# 2017-09-15_drum_circuits.net
KiCad netlist of a schematic drawn in EAGLE
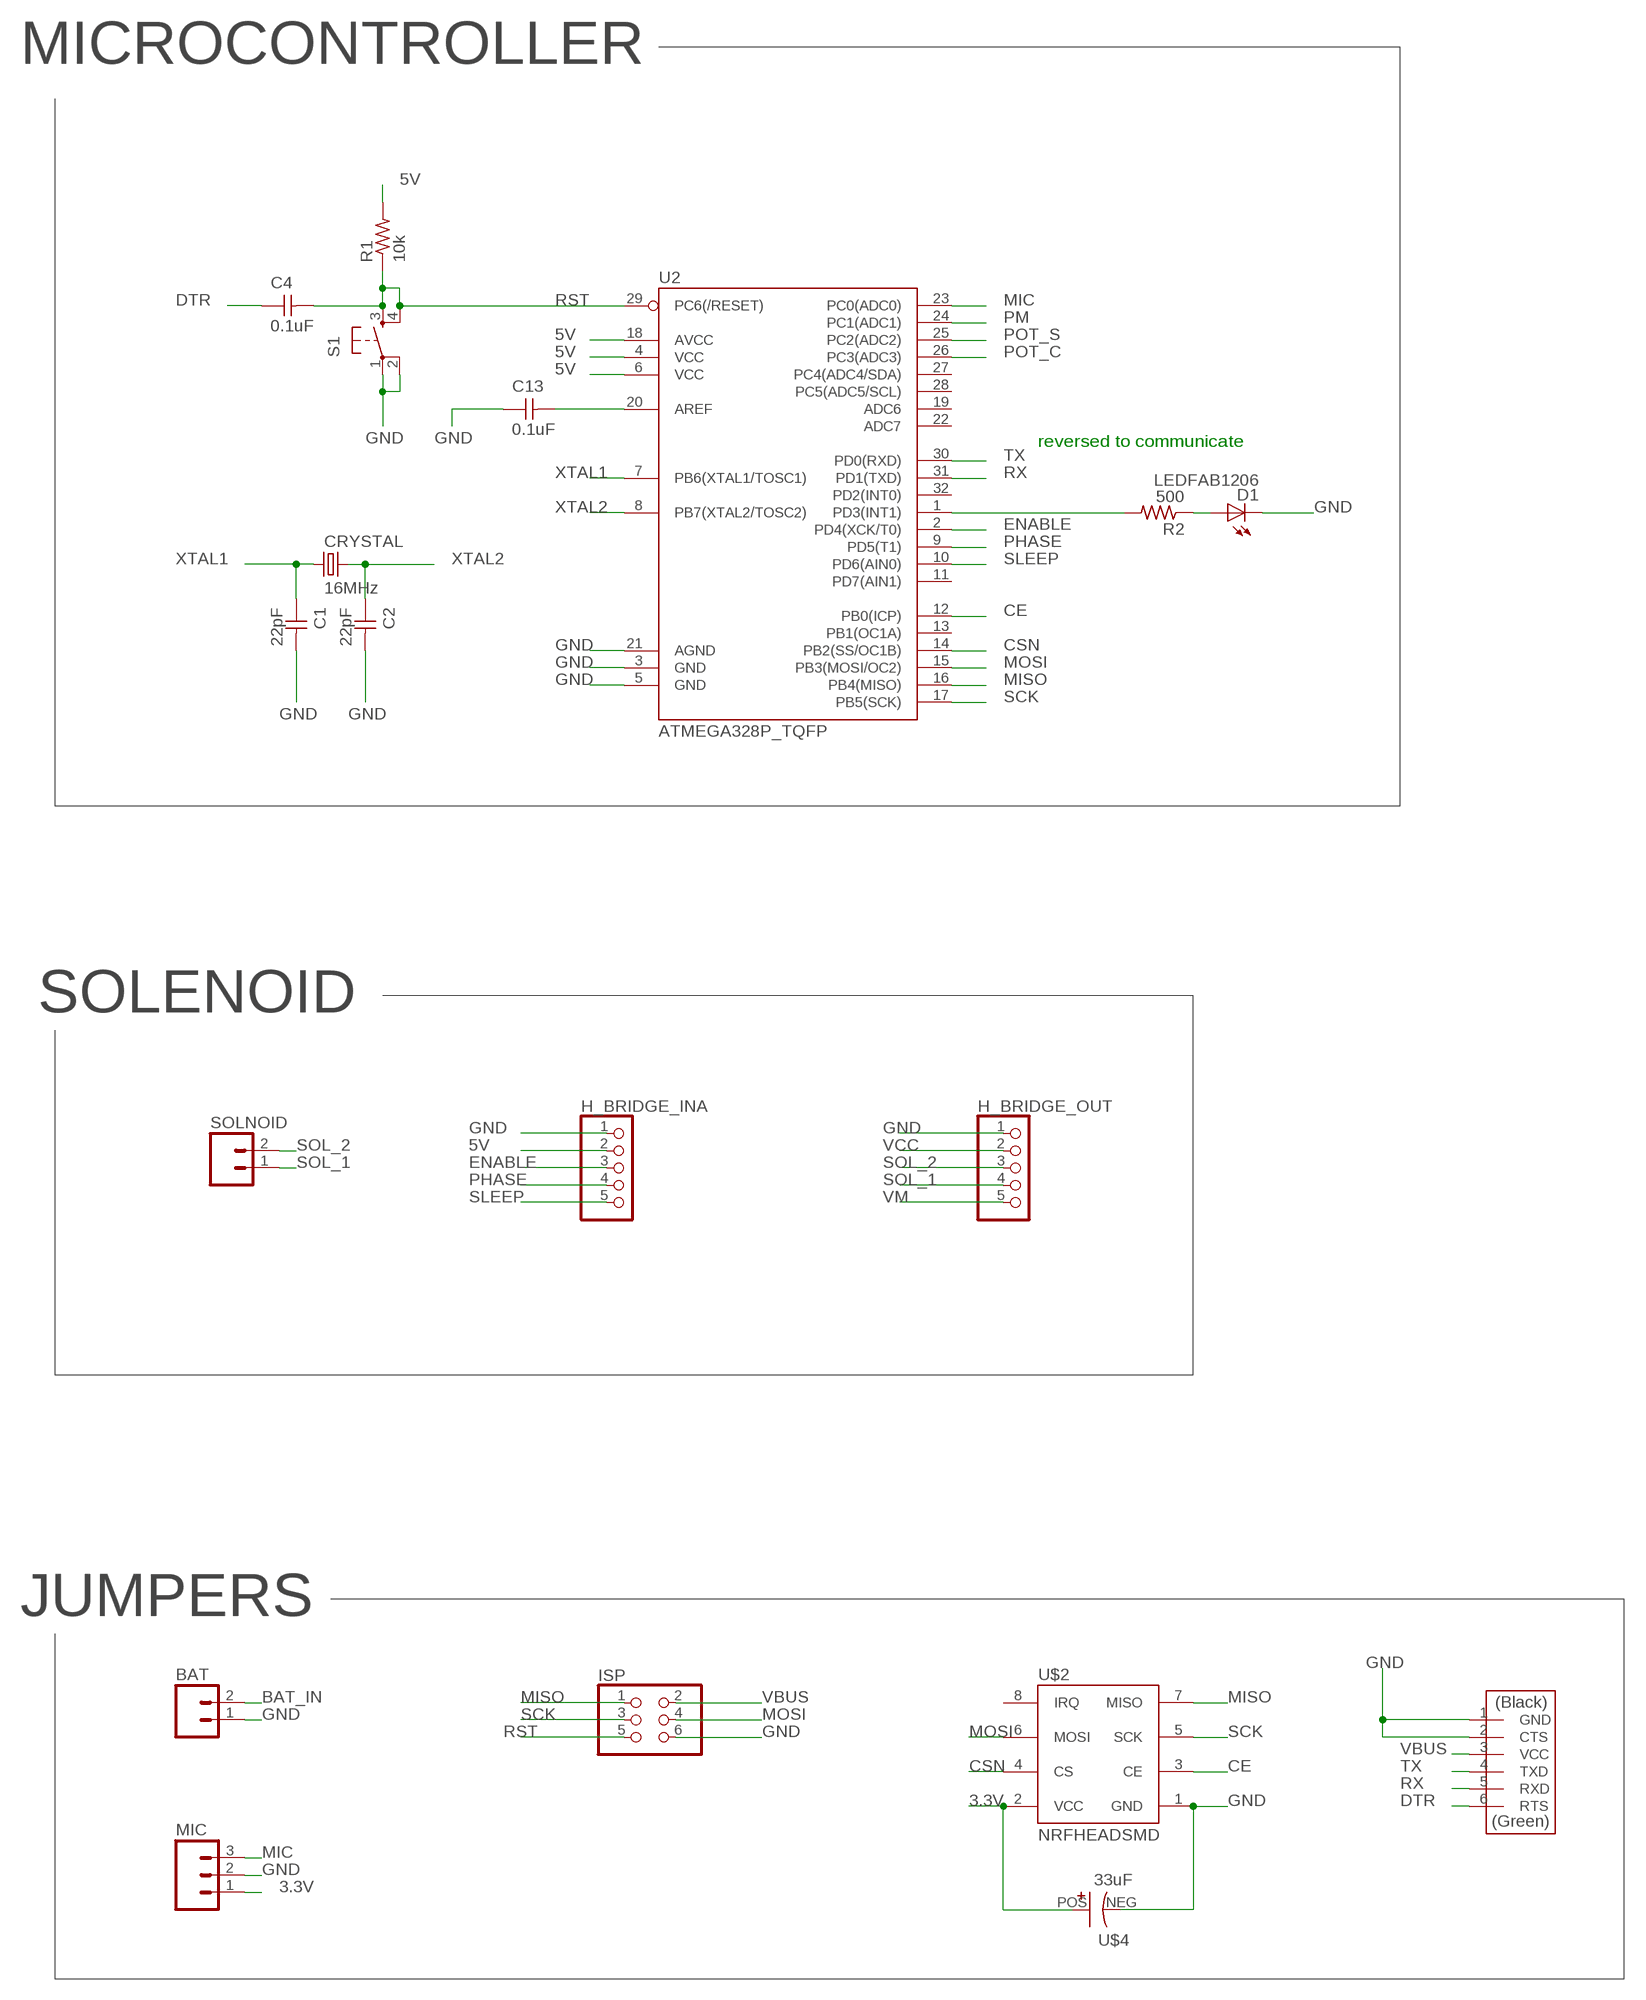
[diagram p0: schematic, sheet 1, part 1 of 2]
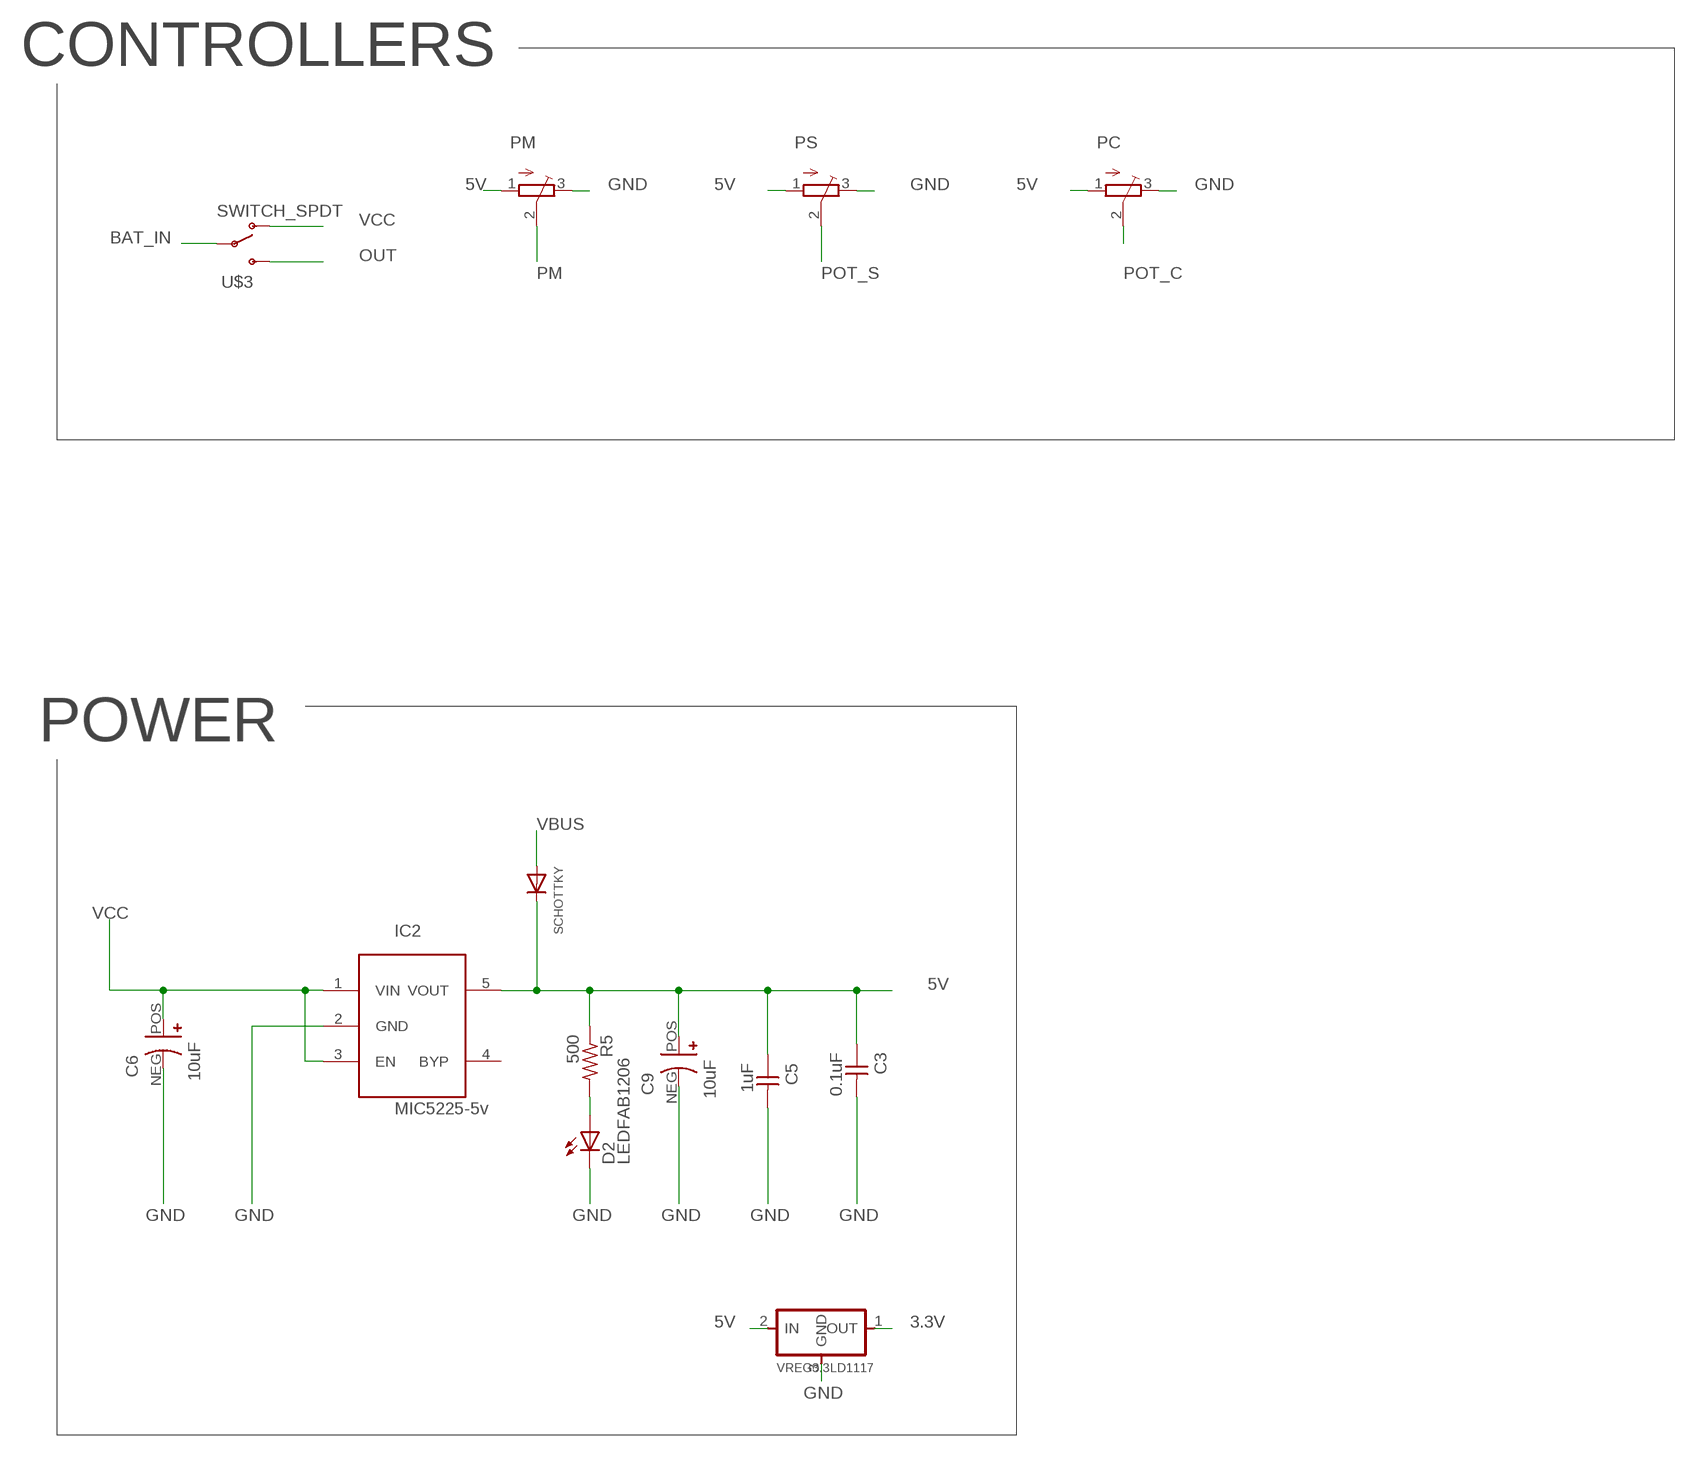
[diagram p1: schematic, sheet 1, part 2 of 2]

(export (version "E")
  (design (tool "Eeschema 10.0.6"))
  (components
    (comp (ref "BAT")
      (value "M02PTH")
      (footprint "eagle-import:1X02")
      (libsource (lib "eagle-import") (part "M02PTH"))
    )
    (comp (ref "C1")
      (value "22pF")
      (footprint "eagle-import:C1206FAB")
      (libsource (lib "eagle-import") (part "CAP-UNPOLARIZEDFAB"))
    )
    (comp (ref "C2")
      (value "22pF")
      (footprint "eagle-import:C1206FAB")
      (libsource (lib "eagle-import") (part "CAP-UNPOLARIZEDFAB"))
    )
    (comp (ref "C3")
      (value "0.1uF")
      (footprint "eagle-import:C1206FAB")
      (libsource (lib "eagle-import") (part "CAP-UNPOLARIZEDFAB"))
    )
    (comp (ref "C4")
      (value "0.1uF")
      (footprint "eagle-import:C1206FAB")
      (libsource (lib "eagle-import") (part "CAP-UNPOLARIZEDFAB"))
    )
    (comp (ref "C5")
      (value "1uF")
      (footprint "eagle-import:C1206FAB")
      (libsource (lib "eagle-import") (part "CAP-UNPOLARIZEDFAB"))
    )
    (comp (ref "C6")
      (value "10uF")
      (footprint "eagle-import:PANASONIC-CAP-SMD-B")
      (libsource (lib "eagle-import") (part "POLCAP-PANASONIC-SMD-B01"))
    )
    (comp (ref "C9")
      (value "10uF")
      (footprint "eagle-import:PANASONIC-CAP-SMD-B")
      (libsource (lib "eagle-import") (part "POLCAP-PANASONIC-SMD-B01"))
    )
    (comp (ref "C13")
      (value "0.1uF")
      (footprint "eagle-import:C1206FAB")
      (libsource (lib "eagle-import") (part "CAP-UNPOLARIZEDFAB"))
    )
    (comp (ref "CRYSTAL")
      (value "16MHz")
      (footprint "eagle-import:2-SMD-5X3MM")
      (libsource (lib "eagle-import") (part "CRYSTAL"))
    )
    (comp (ref "D1")
      (value "LEDFAB1206")
      (footprint "eagle-import:LED1206FAB")
      (libsource (lib "eagle-import") (part "LEDFAB1206"))
    )
    (comp (ref "D2")
      (value "LEDFAB1206")
      (footprint "eagle-import:LED1206FAB")
      (libsource (lib "eagle-import") (part "LEDFAB1206"))
    )
    (comp (ref "H_BRIDGE_INA")
      (value "PINHD-1X05_2.54-SMD")
      (footprint "eagle-import:1X05SMD")
      (libsource (lib "eagle-import") (part "PINHD-1X05_2.54-SMD"))
    )
    (comp (ref "H_BRIDGE_OUT")
      (value "PINHD-1X05_2.54-SMD")
      (footprint "eagle-import:1X05SMD")
      (libsource (lib "eagle-import") (part "PINHD-1X05_2.54-SMD"))
    )
    (comp (ref "IC2")
      (value "MIC5225-5v")
      (footprint "eagle-import:SOT23-5L")
      (libsource (lib "eagle-import") (part "LP298XS"))
    )
    (comp (ref "ISP")
      (value "PINHD-2X3-SMD")
      (footprint "eagle-import:2X03SMD")
      (libsource (lib "eagle-import") (part "PINHD-2X3-SMD"))
    )
    (comp (ref "MIC")
      (value "M03PTH")
      (footprint "eagle-import:1X03")
      (libsource (lib "eagle-import") (part "M03PTH"))
    )
    (comp (ref "PC")
      (value "TRIMPOTTC33X")
      (footprint "eagle-import:TC33X")
      (libsource (lib "eagle-import") (part "TRIMPOTTC33X"))
    )
    (comp (ref "PM")
      (value "TRIMPOTTC33X")
      (footprint "eagle-import:TC33X")
      (libsource (lib "eagle-import") (part "TRIMPOTTC33X"))
    )
    (comp (ref "PS")
      (value "TRIMPOTTC33X")
      (footprint "eagle-import:TC33X")
      (libsource (lib "eagle-import") (part "TRIMPOTTC33X"))
    )
    (comp (ref "R1")
      (value "10k")
      (footprint "eagle-import:R1206FAB")
      (libsource (lib "eagle-import") (part "RES-US1206FAB"))
    )
    (comp (ref "R2")
      (value "500")
      (footprint "eagle-import:R1206FAB")
      (libsource (lib "eagle-import") (part "RES-US1206FAB"))
    )
    (comp (ref "R5")
      (value "500")
      (footprint "eagle-import:R1206FAB")
      (libsource (lib "eagle-import") (part "RES-US1206FAB"))
    )
    (comp (ref "S1")
      (value "6MM_SWITCH6MM_SWITCH")
      (footprint "eagle-import:6MM_SWITCH")
      (libsource (lib "eagle-import") (part "6MM_SWITCH6MM_SWITCH"))
    )
    (comp (ref "SCHOTTKY")
      (value "DIODE_SOD-123FL")
      (footprint "eagle-import:SOD-123FL")
      (libsource (lib "eagle-import") (part "DIODE_SOD-123FL"))
    )
    (comp (ref "SOLNOID")
      (value "M02PTH")
      (footprint "eagle-import:1X02")
      (libsource (lib "eagle-import") (part "M02PTH"))
    )
    (comp (ref "U$1")
      (value "FTDI-SMD-HEADER")
      (footprint "eagle-import:1X06SMD")
      (libsource (lib "eagle-import") (part "FTDI-SMD-HEADER"))
    )
    (comp (ref "U$2")
      (value "NRFHEADSMD")
      (footprint "eagle-import:2.54MM")
      (libsource (lib "eagle-import") (part "NRFHEADSMD"))
    )
    (comp (ref "U$3")
      (value "SWITCH_SPDT")
      (footprint "eagle-import:KPS-1290")
      (libsource (lib "eagle-import") (part "SWITCH_SPDT"))
    )
    (comp (ref "U$4")
      (value "33uF")
      (footprint "eagle-import:PANASONIC-CAP-SMD-C")
      (libsource (lib "eagle-import") (part "POLCAP-PANASONIC-SMD-C"))
    )
    (comp (ref "U2")
      (value "ATMEGA328P_TQFP")
      (footprint "eagle-import:TQFP32-08")
      (libsource (lib "eagle-import") (part "ATMEGA328P_TQFP"))
    )
    (comp (ref "VREG3.3")
      (value "LD1117")
      (footprint "eagle-import:SOT23")
      (libsource (lib "eagle-import") (part "REGULATORSOT23"))
    )
  )
  (nets
    (net (code "1") (name "/3.3V") (class "Default")
      (node (ref "MIC") (pin "1") (pinfunction "1_1") (pintype "passive"))
      (node (ref "U$2") (pin "2") (pinfunction "VCC_2") (pintype "bidirectional"))
      (node (ref "U$4") (pin "POS") (pinfunction "+_POS") (pintype "bidirectional"))
      (node (ref "VREG3.3") (pin "1") (pinfunction "OUT_1") (pintype "bidirectional"))
    )
    (net (code "2") (name "/5V") (class "Default")
      (node (ref "C3") (pin "1") (pinfunction "1_1") (pintype "passive"))
      (node (ref "C5") (pin "1") (pinfunction "1_1") (pintype "passive"))
      (node (ref "C9") (pin "POS") (pinfunction "+_POS") (pintype "bidirectional"))
      (node (ref "H_BRIDGE_INA") (pin "2") (pinfunction "2_2") (pintype "passive"))
      (node (ref "IC2") (pin "5") (pinfunction "VOUT_5") (pintype "bidirectional"))
      (node (ref "PC") (pin "1") (pinfunction "A_1") (pintype "passive"))
      (node (ref "PM") (pin "1") (pinfunction "A_1") (pintype "passive"))
      (node (ref "PS") (pin "1") (pinfunction "A_1") (pintype "passive"))
      (node (ref "R1") (pin "2") (pinfunction "2_2") (pintype "passive"))
      (node (ref "R5") (pin "1") (pinfunction "1_1") (pintype "passive"))
      (node (ref "SCHOTTKY") (pin "C") (pinfunction "C_C") (pintype "passive"))
      (node (ref "U2") (pin "18") (pinfunction "AVCC_18") (pintype "bidirectional"))
      (node (ref "U2") (pin "4") (pinfunction "VCC_4") (pintype "bidirectional"))
      (node (ref "U2") (pin "6") (pinfunction "VCC_6") (pintype "bidirectional"))
      (node (ref "VREG3.3") (pin "2") (pinfunction "IN_2") (pintype "bidirectional"))
    )
    (net (code "3") (name "/BAT_IN") (class "Default")
      (node (ref "BAT") (pin "2") (pinfunction "2_2") (pintype "passive"))
      (node (ref "U$3") (pin "P") (pinfunction "P_P") (pintype "passive"))
    )
    (net (code "4") (name "/CE") (class "Default")
      (node (ref "U$2") (pin "3") (pinfunction "CE_3") (pintype "bidirectional"))
      (node (ref "U2") (pin "12") (pinfunction "PB0(ICP)_12") (pintype "bidirectional"))
    )
    (net (code "5") (name "/CSN") (class "Default")
      (node (ref "U$2") (pin "4") (pinfunction "CS_4") (pintype "bidirectional"))
      (node (ref "U2") (pin "14") (pinfunction "PB2(SS/OC1B)_14") (pintype "bidirectional"))
    )
    (net (code "6") (name "/DTR") (class "Default")
      (node (ref "C4") (pin "1") (pinfunction "1_1") (pintype "passive"))
      (node (ref "U$1") (pin "6") (pinfunction "RTS_6") (pintype "bidirectional"))
    )
    (net (code "7") (name "/ENABLE") (class "Default")
      (node (ref "H_BRIDGE_INA") (pin "3") (pinfunction "3_3") (pintype "passive"))
      (node (ref "U2") (pin "2") (pinfunction "PD4(XCK/T0)_2") (pintype "bidirectional"))
    )
    (net (code "8") (name "/GND") (class "Default")
      (node (ref "BAT") (pin "1") (pinfunction "1_1") (pintype "passive"))
      (node (ref "C1") (pin "2") (pinfunction "2_2") (pintype "passive"))
      (node (ref "C13") (pin "1") (pinfunction "1_1") (pintype "passive"))
      (node (ref "C2") (pin "2") (pinfunction "2_2") (pintype "passive"))
      (node (ref "C3") (pin "2") (pinfunction "2_2") (pintype "passive"))
      (node (ref "C5") (pin "2") (pinfunction "2_2") (pintype "passive"))
      (node (ref "C6") (pin "NEG") (pinfunction "-_NEG") (pintype "bidirectional"))
      (node (ref "C9") (pin "NEG") (pinfunction "-_NEG") (pintype "bidirectional"))
      (node (ref "D1") (pin "2") (pinfunction "C_2") (pintype "passive"))
      (node (ref "D2") (pin "2") (pinfunction "C_2") (pintype "passive"))
      (node (ref "H_BRIDGE_INA") (pin "1") (pinfunction "1_1") (pintype "passive"))
      (node (ref "H_BRIDGE_OUT") (pin "1") (pinfunction "1_1") (pintype "passive"))
      (node (ref "IC2") (pin "2") (pinfunction "GND_2") (pintype "bidirectional"))
      (node (ref "ISP") (pin "6") (pinfunction "6_6") (pintype "passive"))
      (node (ref "MIC") (pin "2") (pinfunction "2_2") (pintype "passive"))
      (node (ref "PC") (pin "3") (pinfunction "E_3") (pintype "passive"))
      (node (ref "PM") (pin "3") (pinfunction "E_3") (pintype "passive"))
      (node (ref "PS") (pin "3") (pinfunction "E_3") (pintype "passive"))
      (node (ref "S1") (pin "1") (pinfunction "P_1") (pintype "passive"))
      (node (ref "S1") (pin "2") (pinfunction "P1_2") (pintype "passive"))
      (node (ref "U$1") (pin "1") (pinfunction "GND_1") (pintype "bidirectional"))
      (node (ref "U$1") (pin "2") (pinfunction "CTS_2") (pintype "bidirectional"))
      (node (ref "U$2") (pin "1") (pinfunction "GND_1") (pintype "bidirectional"))
      (node (ref "U$4") (pin "NEG") (pinfunction "-_NEG") (pintype "bidirectional"))
      (node (ref "U2") (pin "21") (pinfunction "AGND_21") (pintype "bidirectional"))
      (node (ref "U2") (pin "3") (pinfunction "GND_3") (pintype "bidirectional"))
      (node (ref "U2") (pin "5") (pinfunction "GND_5") (pintype "bidirectional"))
      (node (ref "VREG3.3") (pin "3") (pinfunction "GND_3") (pintype "bidirectional"))
    )
    (net (code "9") (name "/MIC") (class "Default")
      (node (ref "MIC") (pin "3") (pinfunction "3_3") (pintype "passive"))
      (node (ref "U2") (pin "23") (pinfunction "PC0(ADC0)_23") (pintype "bidirectional"))
    )
    (net (code "10") (name "/MISO") (class "Default")
      (node (ref "ISP") (pin "1") (pinfunction "1_1") (pintype "passive"))
      (node (ref "U$2") (pin "7") (pinfunction "MISO_7") (pintype "bidirectional"))
      (node (ref "U2") (pin "16") (pinfunction "PB4(MISO)_16") (pintype "bidirectional"))
    )
    (net (code "11") (name "/MOSI") (class "Default")
      (node (ref "ISP") (pin "4") (pinfunction "4_4") (pintype "passive"))
      (node (ref "U$2") (pin "6") (pinfunction "MOSI_6") (pintype "bidirectional"))
      (node (ref "U2") (pin "15") (pinfunction "PB3(MOSI/OC2)_15") (pintype "bidirectional"))
    )
    (net (code "12") (name "/OUT") (class "Default")
      (node (ref "U$3") (pin "S") (pinfunction "S_S") (pintype "passive"))
    )
    (net (code "13") (name "/PHASE") (class "Default")
      (node (ref "H_BRIDGE_INA") (pin "4") (pinfunction "4_4") (pintype "passive"))
      (node (ref "U2") (pin "9") (pinfunction "PD5(T1)_9") (pintype "bidirectional"))
    )
    (net (code "14") (name "/PM") (class "Default")
      (node (ref "PM") (pin "2") (pinfunction "S_2") (pintype "passive"))
      (node (ref "U2") (pin "24") (pinfunction "PC1(ADC1)_24") (pintype "bidirectional"))
    )
    (net (code "15") (name "/POT_C") (class "Default")
      (node (ref "PC") (pin "2") (pinfunction "S_2") (pintype "passive"))
      (node (ref "U2") (pin "26") (pinfunction "PC3(ADC3)_26") (pintype "bidirectional"))
    )
    (net (code "16") (name "/POT_S") (class "Default")
      (node (ref "PS") (pin "2") (pinfunction "S_2") (pintype "passive"))
      (node (ref "U2") (pin "25") (pinfunction "PC2(ADC2)_25") (pintype "bidirectional"))
    )
    (net (code "17") (name "/RST") (class "Default")
      (node (ref "C4") (pin "2") (pinfunction "2_2") (pintype "passive"))
      (node (ref "ISP") (pin "5") (pinfunction "5_5") (pintype "passive"))
      (node (ref "R1") (pin "1") (pinfunction "1_1") (pintype "passive"))
      (node (ref "S1") (pin "3") (pinfunction "S_3") (pintype "passive"))
      (node (ref "S1") (pin "4") (pinfunction "S1_4") (pintype "passive"))
      (node (ref "U2") (pin "29") (pinfunction "PC6(/RESET)_29") (pintype "bidirectional"))
    )
    (net (code "18") (name "/RX") (class "Default")
      (node (ref "U$1") (pin "5") (pinfunction "RXD_5") (pintype "bidirectional"))
      (node (ref "U2") (pin "31") (pinfunction "PD1(TXD)_31") (pintype "bidirectional"))
    )
    (net (code "19") (name "/SCK") (class "Default")
      (node (ref "ISP") (pin "3") (pinfunction "3_3") (pintype "passive"))
      (node (ref "U$2") (pin "5") (pinfunction "SCK_5") (pintype "bidirectional"))
      (node (ref "U2") (pin "17") (pinfunction "PB5(SCK)_17") (pintype "bidirectional"))
    )
    (net (code "20") (name "/SLEEP") (class "Default")
      (node (ref "H_BRIDGE_INA") (pin "5") (pinfunction "5_5") (pintype "passive"))
      (node (ref "U2") (pin "10") (pinfunction "PD6(AIN0)_10") (pintype "bidirectional"))
    )
    (net (code "21") (name "/SOL_1") (class "Default")
      (node (ref "H_BRIDGE_OUT") (pin "4") (pinfunction "4_4") (pintype "passive"))
      (node (ref "SOLNOID") (pin "1") (pinfunction "1_1") (pintype "passive"))
    )
    (net (code "22") (name "/SOL_2") (class "Default")
      (node (ref "H_BRIDGE_OUT") (pin "3") (pinfunction "3_3") (pintype "passive"))
      (node (ref "SOLNOID") (pin "2") (pinfunction "2_2") (pintype "passive"))
    )
    (net (code "23") (name "/TX") (class "Default")
      (node (ref "U$1") (pin "4") (pinfunction "TXD_4") (pintype "bidirectional"))
      (node (ref "U2") (pin "30") (pinfunction "PD0(RXD)_30") (pintype "bidirectional"))
    )
    (net (code "24") (name "/VBUS") (class "Default")
      (node (ref "ISP") (pin "2") (pinfunction "2_2") (pintype "passive"))
      (node (ref "SCHOTTKY") (pin "A") (pinfunction "A_A") (pintype "passive"))
      (node (ref "U$1") (pin "3") (pinfunction "VCC_3") (pintype "bidirectional"))
    )
    (net (code "25") (name "/VCC") (class "Default")
      (node (ref "C6") (pin "POS") (pinfunction "+_POS") (pintype "bidirectional"))
      (node (ref "H_BRIDGE_OUT") (pin "2") (pinfunction "2_2") (pintype "passive"))
      (node (ref "IC2") (pin "1") (pinfunction "VIN_1") (pintype "bidirectional"))
      (node (ref "IC2") (pin "3") (pinfunction "EN_3") (pintype "bidirectional"))
      (node (ref "U$3") (pin "O") (pinfunction "O_O") (pintype "passive"))
    )
    (net (code "26") (name "/VM") (class "Default")
      (node (ref "H_BRIDGE_OUT") (pin "5") (pinfunction "5_5") (pintype "passive"))
    )
    (net (code "27") (name "/XTAL1") (class "Default")
      (node (ref "C1") (pin "1") (pinfunction "1_1") (pintype "passive"))
      (node (ref "CRYSTAL") (pin "P$1") (pinfunction "1_P$1") (pintype "passive"))
      (node (ref "U2") (pin "7") (pinfunction "PB6(XTAL1/TOSC1)_7") (pintype "bidirectional"))
    )
    (net (code "28") (name "/XTAL2") (class "Default")
      (node (ref "C2") (pin "1") (pinfunction "1_1") (pintype "passive"))
      (node (ref "CRYSTAL") (pin "P$2") (pinfunction "2_P$2") (pintype "passive"))
      (node (ref "U2") (pin "8") (pinfunction "PB7(XTAL2/TOSC2)_8") (pintype "bidirectional"))
    )
    (net (code "29") (name "Net-(D1-A)") (class "Default")
      (node (ref "D1") (pin "1") (pinfunction "A_1") (pintype "passive"))
      (node (ref "R2") (pin "1") (pinfunction "1_1") (pintype "passive"))
    )
    (net (code "30") (name "Net-(D2-A)") (class "Default")
      (node (ref "D2") (pin "1") (pinfunction "A_1") (pintype "passive"))
      (node (ref "R5") (pin "2") (pinfunction "2_2") (pintype "passive"))
    )
    (net (code "31") (name "Net-(U2-AREF)") (class "Default")
      (node (ref "C13") (pin "2") (pinfunction "2_2") (pintype "passive"))
      (node (ref "U2") (pin "20") (pinfunction "AREF_20") (pintype "bidirectional"))
    )
    (net (code "32") (name "Net-(U2-PD3(INT1))") (class "Default")
      (node (ref "R2") (pin "2") (pinfunction "2_2") (pintype "passive"))
      (node (ref "U2") (pin "1") (pinfunction "PD3(INT1)_1") (pintype "bidirectional"))
    )
    (net (code "33") (name "unconnected-(IC2-BYP-Pad4)") (class "Default")
      (node (ref "IC2") (pin "4") (pinfunction "BYP_4") (pintype "bidirectional"))
    )
    (net (code "34") (name "unconnected-(U$2-IRQ-Pad8)") (class "Default")
      (node (ref "U$2") (pin "8") (pinfunction "IRQ_8") (pintype "bidirectional"))
    )
    (net (code "35") (name "unconnected-(U2-ADC6-Pad19)") (class "Default")
      (node (ref "U2") (pin "19") (pinfunction "ADC6_19") (pintype "bidirectional"))
    )
    (net (code "36") (name "unconnected-(U2-ADC7-Pad22)") (class "Default")
      (node (ref "U2") (pin "22") (pinfunction "ADC7_22") (pintype "bidirectional"))
    )
    (net (code "37") (name "unconnected-(U2-PB1(OC1A)-Pad13)") (class "Default")
      (node (ref "U2") (pin "13") (pinfunction "PB1(OC1A)_13") (pintype "bidirectional"))
    )
    (net (code "38") (name "unconnected-(U2-PC4(ADC4{slash}SDA)-Pad27)") (class "Default")
      (node (ref "U2") (pin "27") (pinfunction "PC4(ADC4/SDA)_27") (pintype "bidirectional"))
    )
    (net (code "39") (name "unconnected-(U2-PC5(ADC5{slash}SCL)-Pad28)") (class "Default")
      (node (ref "U2") (pin "28") (pinfunction "PC5(ADC5/SCL)_28") (pintype "bidirectional"))
    )
    (net (code "40") (name "unconnected-(U2-PD2(INT0)-Pad32)") (class "Default")
      (node (ref "U2") (pin "32") (pinfunction "PD2(INT0)_32") (pintype "bidirectional"))
    )
    (net (code "41") (name "unconnected-(U2-PD7(AIN1)-Pad11)") (class "Default")
      (node (ref "U2") (pin "11") (pinfunction "PD7(AIN1)_11") (pintype "bidirectional"))
    )
  )
)
